# plinkykeeb2_21Jan2022.net
KiCad netlist of a schematic drawn in EAGLE
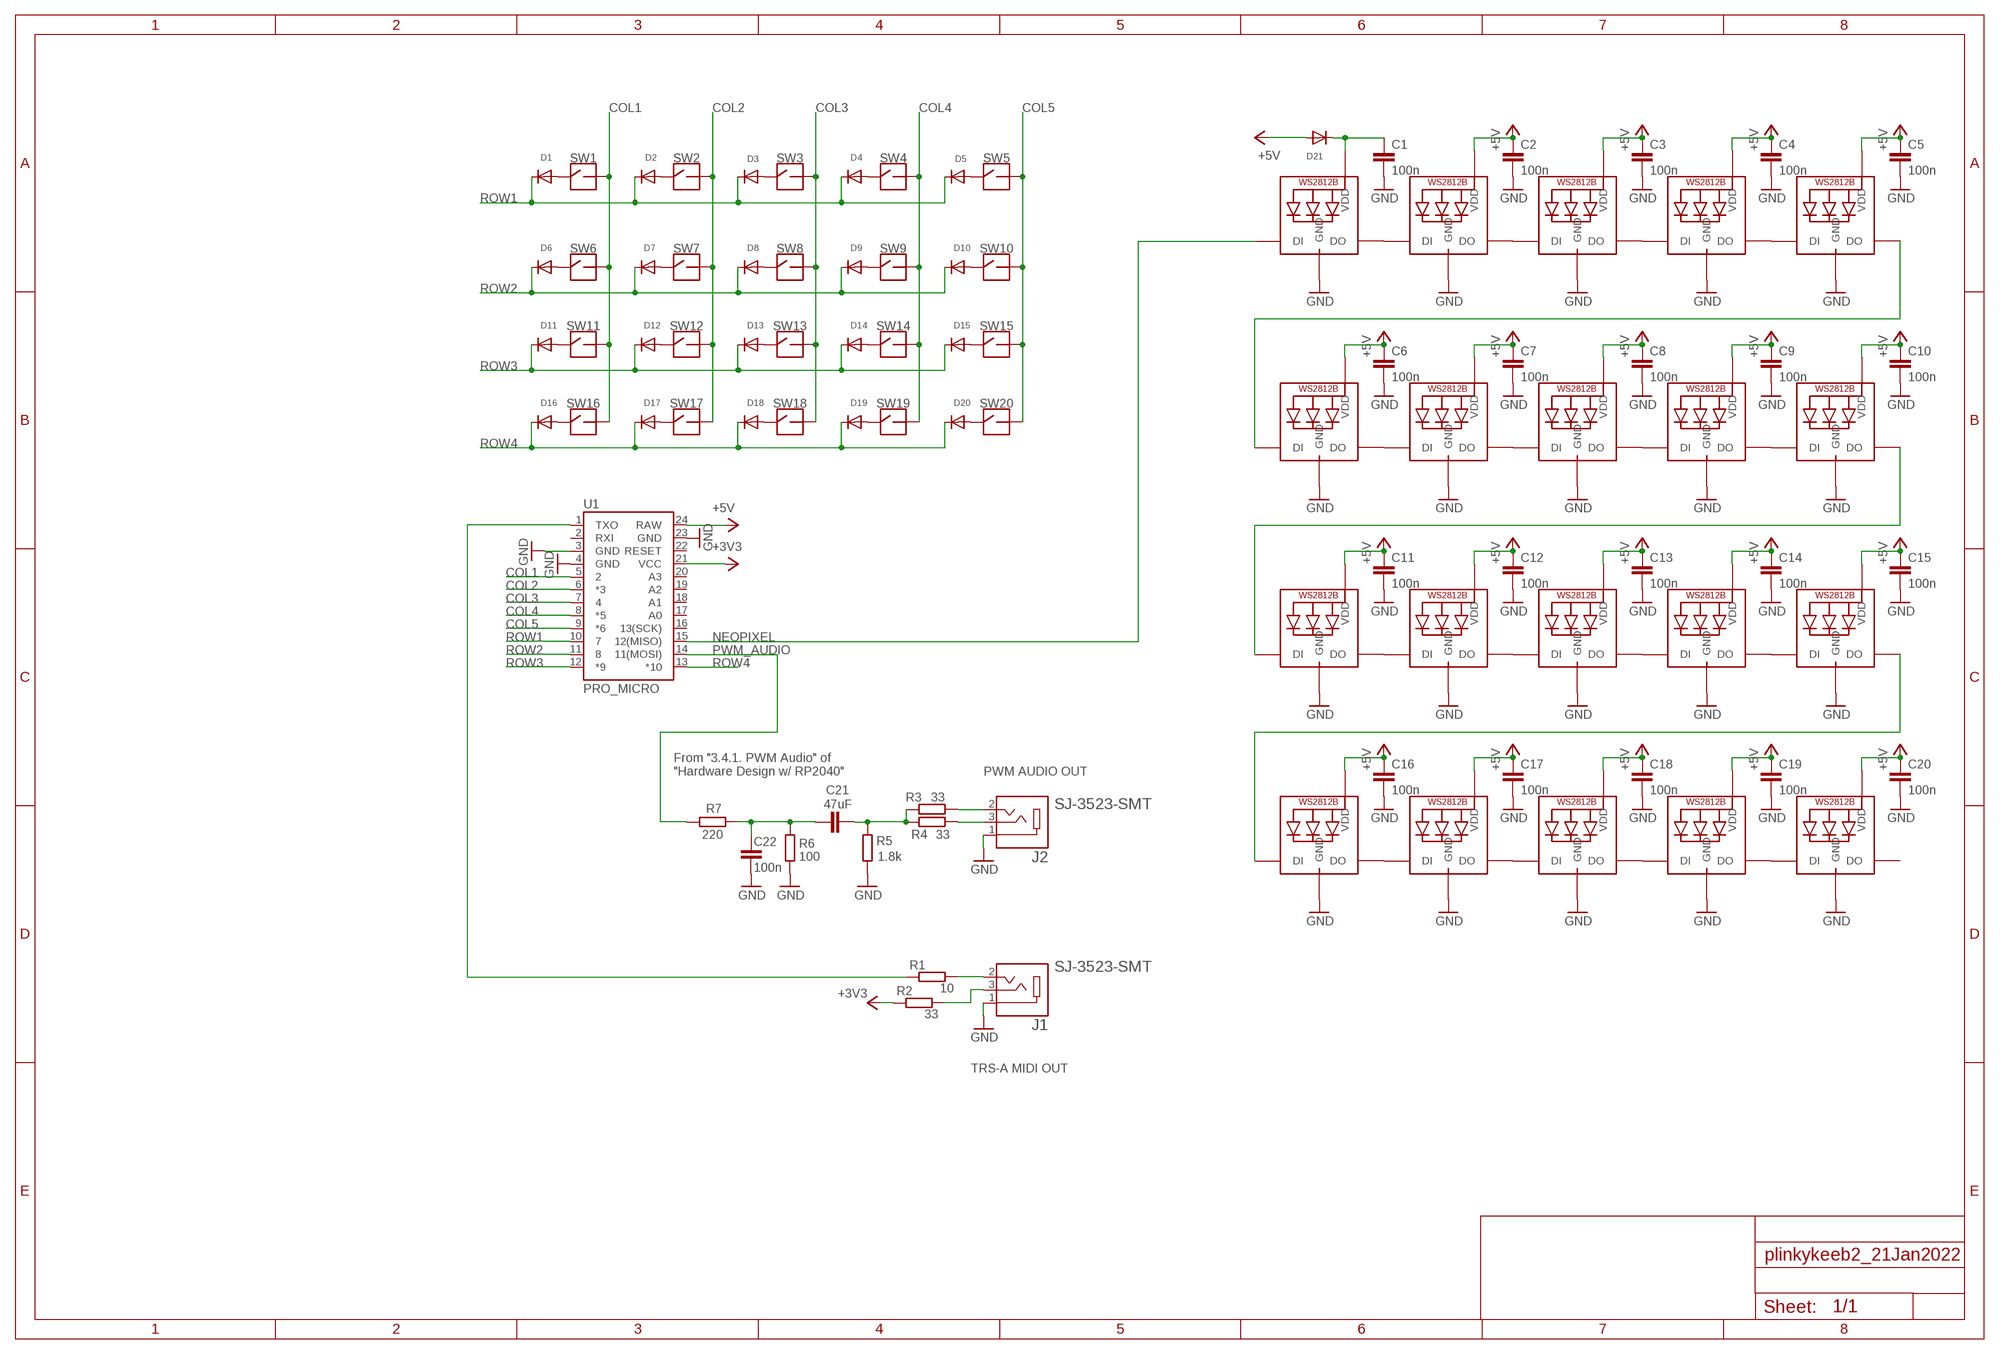
[diagram p0: schematic, sheet 1]

(export (version "E")
  (design (tool "Eeschema 10.0.6"))
  (components
    (comp (ref "C1")
      (value "100n")
      (footprint "eagle-import:C025-024X044")
      (libsource (lib "eagle-import") (part "C-EU025-024X044"))
    )
    (comp (ref "C2")
      (value "100n")
      (footprint "eagle-import:C025-024X044")
      (libsource (lib "eagle-import") (part "C-EU025-024X044"))
    )
    (comp (ref "C3")
      (value "100n")
      (footprint "eagle-import:C025-024X044")
      (libsource (lib "eagle-import") (part "C-EU025-024X044"))
    )
    (comp (ref "C4")
      (value "100n")
      (footprint "eagle-import:C025-024X044")
      (libsource (lib "eagle-import") (part "C-EU025-024X044"))
    )
    (comp (ref "C5")
      (value "100n")
      (footprint "eagle-import:C025-024X044")
      (libsource (lib "eagle-import") (part "C-EU025-024X044"))
    )
    (comp (ref "C6")
      (value "100n")
      (footprint "eagle-import:C025-024X044")
      (libsource (lib "eagle-import") (part "C-EU025-024X044"))
    )
    (comp (ref "C7")
      (value "100n")
      (footprint "eagle-import:C025-024X044")
      (libsource (lib "eagle-import") (part "C-EU025-024X044"))
    )
    (comp (ref "C8")
      (value "100n")
      (footprint "eagle-import:C025-024X044")
      (libsource (lib "eagle-import") (part "C-EU025-024X044"))
    )
    (comp (ref "C9")
      (value "100n")
      (footprint "eagle-import:C025-024X044")
      (libsource (lib "eagle-import") (part "C-EU025-024X044"))
    )
    (comp (ref "C10")
      (value "100n")
      (footprint "eagle-import:C025-024X044")
      (libsource (lib "eagle-import") (part "C-EU025-024X044"))
    )
    (comp (ref "C11")
      (value "100n")
      (footprint "eagle-import:C025-024X044")
      (libsource (lib "eagle-import") (part "C-EU025-024X044"))
    )
    (comp (ref "C12")
      (value "100n")
      (footprint "eagle-import:C025-024X044")
      (libsource (lib "eagle-import") (part "C-EU025-024X044"))
    )
    (comp (ref "C13")
      (value "100n")
      (footprint "eagle-import:C025-024X044")
      (libsource (lib "eagle-import") (part "C-EU025-024X044"))
    )
    (comp (ref "C14")
      (value "100n")
      (footprint "eagle-import:C025-024X044")
      (libsource (lib "eagle-import") (part "C-EU025-024X044"))
    )
    (comp (ref "C15")
      (value "100n")
      (footprint "eagle-import:C025-024X044")
      (libsource (lib "eagle-import") (part "C-EU025-024X044"))
    )
    (comp (ref "C16")
      (value "100n")
      (footprint "eagle-import:C025-024X044")
      (libsource (lib "eagle-import") (part "C-EU025-024X044"))
    )
    (comp (ref "C17")
      (value "100n")
      (footprint "eagle-import:C025-024X044")
      (libsource (lib "eagle-import") (part "C-EU025-024X044"))
    )
    (comp (ref "C18")
      (value "100n")
      (footprint "eagle-import:C025-024X044")
      (libsource (lib "eagle-import") (part "C-EU025-024X044"))
    )
    (comp (ref "C19")
      (value "100n")
      (footprint "eagle-import:C025-024X044")
      (libsource (lib "eagle-import") (part "C-EU025-024X044"))
    )
    (comp (ref "C20")
      (value "100n")
      (footprint "eagle-import:C025-024X044")
      (libsource (lib "eagle-import") (part "C-EU025-024X044"))
    )
    (comp (ref "C21")
      (value "47uF")
      (footprint "eagle-import:C0805")
      (libsource (lib "eagle-import") (part "C-EUC0805"))
    )
    (comp (ref "C22")
      (value "100n")
      (footprint "eagle-import:C0805")
      (libsource (lib "eagle-import") (part "C-EUC0805"))
    )
    (comp (ref "D1")
      (value "DIODEDO-1N4148")
      (footprint "eagle-import:DO-1N4148")
      (libsource (lib "eagle-import") (part "DIODEDO-1N4148"))
    )
    (comp (ref "D2")
      (value "DIODEDO-1N4148")
      (footprint "eagle-import:DO-1N4148")
      (libsource (lib "eagle-import") (part "DIODEDO-1N4148"))
    )
    (comp (ref "D3")
      (value "DIODEDO-1N4148")
      (footprint "eagle-import:DO-1N4148")
      (libsource (lib "eagle-import") (part "DIODEDO-1N4148"))
    )
    (comp (ref "D4")
      (value "DIODEDO-1N4148")
      (footprint "eagle-import:DO-1N4148")
      (libsource (lib "eagle-import") (part "DIODEDO-1N4148"))
    )
    (comp (ref "D5")
      (value "DIODEDO-1N4148")
      (footprint "eagle-import:DO-1N4148")
      (libsource (lib "eagle-import") (part "DIODEDO-1N4148"))
    )
    (comp (ref "D6")
      (value "DIODEDO-1N4148")
      (footprint "eagle-import:DO-1N4148")
      (libsource (lib "eagle-import") (part "DIODEDO-1N4148"))
    )
    (comp (ref "D7")
      (value "DIODEDO-1N4148")
      (footprint "eagle-import:DO-1N4148")
      (libsource (lib "eagle-import") (part "DIODEDO-1N4148"))
    )
    (comp (ref "D8")
      (value "DIODEDO-1N4148")
      (footprint "eagle-import:DO-1N4148")
      (libsource (lib "eagle-import") (part "DIODEDO-1N4148"))
    )
    (comp (ref "D9")
      (value "DIODEDO-1N4148")
      (footprint "eagle-import:DO-1N4148")
      (libsource (lib "eagle-import") (part "DIODEDO-1N4148"))
    )
    (comp (ref "D10")
      (value "DIODEDO-1N4148")
      (footprint "eagle-import:DO-1N4148")
      (libsource (lib "eagle-import") (part "DIODEDO-1N4148"))
    )
    (comp (ref "D11")
      (value "DIODEDO-1N4148")
      (footprint "eagle-import:DO-1N4148")
      (libsource (lib "eagle-import") (part "DIODEDO-1N4148"))
    )
    (comp (ref "D12")
      (value "DIODEDO-1N4148")
      (footprint "eagle-import:DO-1N4148")
      (libsource (lib "eagle-import") (part "DIODEDO-1N4148"))
    )
    (comp (ref "D13")
      (value "DIODEDO-1N4148")
      (footprint "eagle-import:DO-1N4148")
      (libsource (lib "eagle-import") (part "DIODEDO-1N4148"))
    )
    (comp (ref "D14")
      (value "DIODEDO-1N4148")
      (footprint "eagle-import:DO-1N4148")
      (libsource (lib "eagle-import") (part "DIODEDO-1N4148"))
    )
    (comp (ref "D15")
      (value "DIODEDO-1N4148")
      (footprint "eagle-import:DO-1N4148")
      (libsource (lib "eagle-import") (part "DIODEDO-1N4148"))
    )
    (comp (ref "D16")
      (value "DIODEDO-1N4148")
      (footprint "eagle-import:DO-1N4148")
      (libsource (lib "eagle-import") (part "DIODEDO-1N4148"))
    )
    (comp (ref "D17")
      (value "DIODEDO-1N4148")
      (footprint "eagle-import:DO-1N4148")
      (libsource (lib "eagle-import") (part "DIODEDO-1N4148"))
    )
    (comp (ref "D18")
      (value "DIODEDO-1N4148")
      (footprint "eagle-import:DO-1N4148")
      (libsource (lib "eagle-import") (part "DIODEDO-1N4148"))
    )
    (comp (ref "D19")
      (value "DIODEDO-1N4148")
      (footprint "eagle-import:DO-1N4148")
      (libsource (lib "eagle-import") (part "DIODEDO-1N4148"))
    )
    (comp (ref "D20")
      (value "DIODEDO-1N4148")
      (footprint "eagle-import:DO-1N4148")
      (libsource (lib "eagle-import") (part "DIODEDO-1N4148"))
    )
    (comp (ref "D21")
      (value "DIODEDO-1N4148")
      (footprint "eagle-import:DO-1N4148")
      (libsource (lib "eagle-import") (part "DIODEDO-1N4148"))
    )
    (comp (ref "J1")
      (value "SJ-3523-SMT")
      (footprint "eagle-import:CUI_SJ-3523-SMT")
      (fields
        (field (name "DIGI-KEY_PART_NUMBER") "CP-3523SJCT-ND")
        (field (name "MF") "CUI Devices")
        (field (name "MP") "SJ-3523-SMT-TR")
      )
      (libsource (lib "eagle-import") (part "SJ-3523-SMT"))
    )
    (comp (ref "J2")
      (value "SJ-3523-SMT")
      (footprint "eagle-import:CUI_SJ-3523-SMT")
      (fields
        (field (name "DIGI-KEY_PART_NUMBER") "CP-3523SJCT-ND")
        (field (name "MF") "CUI Devices")
        (field (name "MP") "SJ-3523-SMT-TR")
      )
      (libsource (lib "eagle-import") (part "SJ-3523-SMT"))
    )
    (comp (ref "LED1")
      (value "MICROBUILDER_WS2812B_SK6812E")
      (footprint "eagle-import:MICROBUILDER_NEO3535_REVERSE")
      (libsource (lib "eagle-import") (part "MICROBUILDER_WS2812B_SK6812E"))
    )
    (comp (ref "LED2")
      (value "MICROBUILDER_WS2812B_SK6812E")
      (footprint "eagle-import:MICROBUILDER_NEO3535_REVERSE")
      (libsource (lib "eagle-import") (part "MICROBUILDER_WS2812B_SK6812E"))
    )
    (comp (ref "LED3")
      (value "MICROBUILDER_WS2812B_SK6812E")
      (footprint "eagle-import:MICROBUILDER_NEO3535_REVERSE")
      (libsource (lib "eagle-import") (part "MICROBUILDER_WS2812B_SK6812E"))
    )
    (comp (ref "LED4")
      (value "MICROBUILDER_WS2812B_SK6812E")
      (footprint "eagle-import:MICROBUILDER_NEO3535_REVERSE")
      (libsource (lib "eagle-import") (part "MICROBUILDER_WS2812B_SK6812E"))
    )
    (comp (ref "LED5")
      (value "MICROBUILDER_WS2812B_SK6812E")
      (footprint "eagle-import:MICROBUILDER_NEO3535_REVERSE")
      (libsource (lib "eagle-import") (part "MICROBUILDER_WS2812B_SK6812E"))
    )
    (comp (ref "LED6")
      (value "MICROBUILDER_WS2812B_SK6812E")
      (footprint "eagle-import:MICROBUILDER_NEO3535_REVERSE")
      (libsource (lib "eagle-import") (part "MICROBUILDER_WS2812B_SK6812E"))
    )
    (comp (ref "LED7")
      (value "MICROBUILDER_WS2812B_SK6812E")
      (footprint "eagle-import:MICROBUILDER_NEO3535_REVERSE")
      (libsource (lib "eagle-import") (part "MICROBUILDER_WS2812B_SK6812E"))
    )
    (comp (ref "LED8")
      (value "MICROBUILDER_WS2812B_SK6812E")
      (footprint "eagle-import:MICROBUILDER_NEO3535_REVERSE")
      (libsource (lib "eagle-import") (part "MICROBUILDER_WS2812B_SK6812E"))
    )
    (comp (ref "LED9")
      (value "MICROBUILDER_WS2812B_SK6812E")
      (footprint "eagle-import:MICROBUILDER_NEO3535_REVERSE")
      (libsource (lib "eagle-import") (part "MICROBUILDER_WS2812B_SK6812E"))
    )
    (comp (ref "LED10")
      (value "MICROBUILDER_WS2812B_SK6812E")
      (footprint "eagle-import:MICROBUILDER_NEO3535_REVERSE")
      (libsource (lib "eagle-import") (part "MICROBUILDER_WS2812B_SK6812E"))
    )
    (comp (ref "LED11")
      (value "MICROBUILDER_WS2812B_SK6812E")
      (footprint "eagle-import:MICROBUILDER_NEO3535_REVERSE")
      (libsource (lib "eagle-import") (part "MICROBUILDER_WS2812B_SK6812E"))
    )
    (comp (ref "LED12")
      (value "MICROBUILDER_WS2812B_SK6812E")
      (footprint "eagle-import:MICROBUILDER_NEO3535_REVERSE")
      (libsource (lib "eagle-import") (part "MICROBUILDER_WS2812B_SK6812E"))
    )
    (comp (ref "LED13")
      (value "MICROBUILDER_WS2812B_SK6812E")
      (footprint "eagle-import:MICROBUILDER_NEO3535_REVERSE")
      (libsource (lib "eagle-import") (part "MICROBUILDER_WS2812B_SK6812E"))
    )
    (comp (ref "LED14")
      (value "MICROBUILDER_WS2812B_SK6812E")
      (footprint "eagle-import:MICROBUILDER_NEO3535_REVERSE")
      (libsource (lib "eagle-import") (part "MICROBUILDER_WS2812B_SK6812E"))
    )
    (comp (ref "LED15")
      (value "MICROBUILDER_WS2812B_SK6812E")
      (footprint "eagle-import:MICROBUILDER_NEO3535_REVERSE")
      (libsource (lib "eagle-import") (part "MICROBUILDER_WS2812B_SK6812E"))
    )
    (comp (ref "LED16")
      (value "MICROBUILDER_WS2812B_SK6812E")
      (footprint "eagle-import:MICROBUILDER_NEO3535_REVERSE")
      (libsource (lib "eagle-import") (part "MICROBUILDER_WS2812B_SK6812E"))
    )
    (comp (ref "LED17")
      (value "MICROBUILDER_WS2812B_SK6812E")
      (footprint "eagle-import:MICROBUILDER_NEO3535_REVERSE")
      (libsource (lib "eagle-import") (part "MICROBUILDER_WS2812B_SK6812E"))
    )
    (comp (ref "LED18")
      (value "MICROBUILDER_WS2812B_SK6812E")
      (footprint "eagle-import:MICROBUILDER_NEO3535_REVERSE")
      (libsource (lib "eagle-import") (part "MICROBUILDER_WS2812B_SK6812E"))
    )
    (comp (ref "LED19")
      (value "MICROBUILDER_WS2812B_SK6812E")
      (footprint "eagle-import:MICROBUILDER_NEO3535_REVERSE")
      (libsource (lib "eagle-import") (part "MICROBUILDER_WS2812B_SK6812E"))
    )
    (comp (ref "LED20")
      (value "MICROBUILDER_WS2812B_SK6812E")
      (footprint "eagle-import:MICROBUILDER_NEO3535_REVERSE")
      (libsource (lib "eagle-import") (part "MICROBUILDER_WS2812B_SK6812E"))
    )
    (comp (ref "R1")
      (value "10")
      (footprint "eagle-import:R0805")
      (libsource (lib "eagle-import") (part "R-EU_R0805"))
    )
    (comp (ref "R2")
      (value "33")
      (footprint "eagle-import:R0805")
      (libsource (lib "eagle-import") (part "R-EU_R0805"))
    )
    (comp (ref "R3")
      (value "33")
      (footprint "eagle-import:R0805")
      (libsource (lib "eagle-import") (part "R-EU_R0805"))
    )
    (comp (ref "R4")
      (value "33")
      (footprint "eagle-import:R0805")
      (libsource (lib "eagle-import") (part "R-EU_R0805"))
    )
    (comp (ref "R5")
      (value "1.8k")
      (footprint "eagle-import:R0805")
      (libsource (lib "eagle-import") (part "R-EU_R0805"))
    )
    (comp (ref "R6")
      (value "100")
      (footprint "eagle-import:R0805")
      (libsource (lib "eagle-import") (part "R-EU_R0805"))
    )
    (comp (ref "R7")
      (value "220")
      (footprint "eagle-import:R0805")
      (libsource (lib "eagle-import") (part "R-EU_R0805"))
    )
    (comp (ref "SW1")
      (value "KAILH_SOCKETBOX_JADE")
      (footprint "eagle-import:ADAFRUIT_ELECTROMECH_KAILH_SOCKET")
      (libsource (lib "eagle-import") (part "ADAFRUIT_ELECTROMECH_KBD_SWITCH_KAILH_SOCKETBOX_JADE_KAILH_SOCKET"))
    )
    (comp (ref "SW2")
      (value "KAILH_SOCKETBOX_JADE")
      (footprint "eagle-import:ADAFRUIT_ELECTROMECH_KAILH_SOCKET")
      (libsource (lib "eagle-import") (part "ADAFRUIT_ELECTROMECH_KBD_SWITCH_KAILH_SOCKETBOX_JADE_KAILH_SOCKET"))
    )
    (comp (ref "SW3")
      (value "KAILH_SOCKETBOX_JADE")
      (footprint "eagle-import:ADAFRUIT_ELECTROMECH_KAILH_SOCKET")
      (libsource (lib "eagle-import") (part "ADAFRUIT_ELECTROMECH_KBD_SWITCH_KAILH_SOCKETBOX_JADE_KAILH_SOCKET"))
    )
    (comp (ref "SW4")
      (value "KAILH_SOCKETBOX_JADE")
      (footprint "eagle-import:ADAFRUIT_ELECTROMECH_KAILH_SOCKET")
      (libsource (lib "eagle-import") (part "ADAFRUIT_ELECTROMECH_KBD_SWITCH_KAILH_SOCKETBOX_JADE_KAILH_SOCKET"))
    )
    (comp (ref "SW5")
      (value "KAILH_SOCKETBOX_JADE")
      (footprint "eagle-import:ADAFRUIT_ELECTROMECH_KAILH_SOCKET")
      (libsource (lib "eagle-import") (part "ADAFRUIT_ELECTROMECH_KBD_SWITCH_KAILH_SOCKETBOX_JADE_KAILH_SOCKET"))
    )
    (comp (ref "SW6")
      (value "KAILH_SOCKETBOX_JADE")
      (footprint "eagle-import:ADAFRUIT_ELECTROMECH_KAILH_SOCKET")
      (libsource (lib "eagle-import") (part "ADAFRUIT_ELECTROMECH_KBD_SWITCH_KAILH_SOCKETBOX_JADE_KAILH_SOCKET"))
    )
    (comp (ref "SW7")
      (value "KAILH_SOCKETBOX_JADE")
      (footprint "eagle-import:ADAFRUIT_ELECTROMECH_KAILH_SOCKET")
      (libsource (lib "eagle-import") (part "ADAFRUIT_ELECTROMECH_KBD_SWITCH_KAILH_SOCKETBOX_JADE_KAILH_SOCKET"))
    )
    (comp (ref "SW8")
      (value "KAILH_SOCKETBOX_JADE")
      (footprint "eagle-import:ADAFRUIT_ELECTROMECH_KAILH_SOCKET")
      (libsource (lib "eagle-import") (part "ADAFRUIT_ELECTROMECH_KBD_SWITCH_KAILH_SOCKETBOX_JADE_KAILH_SOCKET"))
    )
    (comp (ref "SW9")
      (value "KAILH_SOCKETBOX_JADE")
      (footprint "eagle-import:ADAFRUIT_ELECTROMECH_KAILH_SOCKET")
      (libsource (lib "eagle-import") (part "ADAFRUIT_ELECTROMECH_KBD_SWITCH_KAILH_SOCKETBOX_JADE_KAILH_SOCKET"))
    )
    (comp (ref "SW10")
      (value "KAILH_SOCKETBOX_JADE")
      (footprint "eagle-import:ADAFRUIT_ELECTROMECH_KAILH_SOCKET")
      (libsource (lib "eagle-import") (part "ADAFRUIT_ELECTROMECH_KBD_SWITCH_KAILH_SOCKETBOX_JADE_KAILH_SOCKET"))
    )
    (comp (ref "SW11")
      (value "KAILH_SOCKETBOX_JADE")
      (footprint "eagle-import:ADAFRUIT_ELECTROMECH_KAILH_SOCKET")
      (libsource (lib "eagle-import") (part "ADAFRUIT_ELECTROMECH_KBD_SWITCH_KAILH_SOCKETBOX_JADE_KAILH_SOCKET"))
    )
    (comp (ref "SW12")
      (value "KAILH_SOCKETBOX_JADE")
      (footprint "eagle-import:ADAFRUIT_ELECTROMECH_KAILH_SOCKET")
      (libsource (lib "eagle-import") (part "ADAFRUIT_ELECTROMECH_KBD_SWITCH_KAILH_SOCKETBOX_JADE_KAILH_SOCKET"))
    )
    (comp (ref "SW13")
      (value "KAILH_SOCKETBOX_JADE")
      (footprint "eagle-import:ADAFRUIT_ELECTROMECH_KAILH_SOCKET")
      (libsource (lib "eagle-import") (part "ADAFRUIT_ELECTROMECH_KBD_SWITCH_KAILH_SOCKETBOX_JADE_KAILH_SOCKET"))
    )
    (comp (ref "SW14")
      (value "KAILH_SOCKETBOX_JADE")
      (footprint "eagle-import:ADAFRUIT_ELECTROMECH_KAILH_SOCKET")
      (libsource (lib "eagle-import") (part "ADAFRUIT_ELECTROMECH_KBD_SWITCH_KAILH_SOCKETBOX_JADE_KAILH_SOCKET"))
    )
    (comp (ref "SW15")
      (value "KAILH_SOCKETBOX_JADE")
      (footprint "eagle-import:ADAFRUIT_ELECTROMECH_KAILH_SOCKET")
      (libsource (lib "eagle-import") (part "ADAFRUIT_ELECTROMECH_KBD_SWITCH_KAILH_SOCKETBOX_JADE_KAILH_SOCKET"))
    )
    (comp (ref "SW16")
      (value "KAILH_SOCKETBOX_JADE")
      (footprint "eagle-import:ADAFRUIT_ELECTROMECH_KAILH_SOCKET")
      (libsource (lib "eagle-import") (part "ADAFRUIT_ELECTROMECH_KBD_SWITCH_KAILH_SOCKETBOX_JADE_KAILH_SOCKET"))
    )
    (comp (ref "SW17")
      (value "KAILH_SOCKETBOX_JADE")
      (footprint "eagle-import:ADAFRUIT_ELECTROMECH_KAILH_SOCKET")
      (libsource (lib "eagle-import") (part "ADAFRUIT_ELECTROMECH_KBD_SWITCH_KAILH_SOCKETBOX_JADE_KAILH_SOCKET"))
    )
    (comp (ref "SW18")
      (value "KAILH_SOCKETBOX_JADE")
      (footprint "eagle-import:ADAFRUIT_ELECTROMECH_KAILH_SOCKET")
      (libsource (lib "eagle-import") (part "ADAFRUIT_ELECTROMECH_KBD_SWITCH_KAILH_SOCKETBOX_JADE_KAILH_SOCKET"))
    )
    (comp (ref "SW19")
      (value "KAILH_SOCKETBOX_JADE")
      (footprint "eagle-import:ADAFRUIT_ELECTROMECH_KAILH_SOCKET")
      (libsource (lib "eagle-import") (part "ADAFRUIT_ELECTROMECH_KBD_SWITCH_KAILH_SOCKETBOX_JADE_KAILH_SOCKET"))
    )
    (comp (ref "SW20")
      (value "KAILH_SOCKETBOX_JADE")
      (footprint "eagle-import:ADAFRUIT_ELECTROMECH_KAILH_SOCKET")
      (libsource (lib "eagle-import") (part "ADAFRUIT_ELECTROMECH_KBD_SWITCH_KAILH_SOCKETBOX_JADE_KAILH_SOCKET"))
    )
    (comp (ref "U1")
      (value "PRO_MICRO")
      (footprint "eagle-import:SPARKFUN_PRO_MICRO")
      (libsource (lib "eagle-import") (part "SPARKFUN_PRO_MICRO"))
    )
  )
  (nets
    (net (code "1") (name "+3V3") (class "Default")
      (node (ref "R2") (pin "2") (pinfunction "2_2") (pintype "passive"))
      (node (ref "U1") (pin "21") (pinfunction "VCC_21") (pintype "power_in"))
    )
    (net (code "2") (name "+5V") (class "Default")
      (node (ref "C10") (pin "1") (pinfunction "1_1") (pintype "passive"))
      (node (ref "C11") (pin "1") (pinfunction "1_1") (pintype "passive"))
      (node (ref "C12") (pin "1") (pinfunction "1_1") (pintype "passive"))
      (node (ref "C13") (pin "1") (pinfunction "1_1") (pintype "passive"))
      (node (ref "C14") (pin "1") (pinfunction "1_1") (pintype "passive"))
      (node (ref "C15") (pin "1") (pinfunction "1_1") (pintype "passive"))
      (node (ref "C16") (pin "1") (pinfunction "1_1") (pintype "passive"))
      (node (ref "C17") (pin "1") (pinfunction "1_1") (pintype "passive"))
      (node (ref "C18") (pin "1") (pinfunction "1_1") (pintype "passive"))
      (node (ref "C19") (pin "1") (pinfunction "1_1") (pintype "passive"))
      (node (ref "C2") (pin "1") (pinfunction "1_1") (pintype "passive"))
      (node (ref "C20") (pin "1") (pinfunction "1_1") (pintype "passive"))
      (node (ref "C3") (pin "1") (pinfunction "1_1") (pintype "passive"))
      (node (ref "C4") (pin "1") (pinfunction "1_1") (pintype "passive"))
      (node (ref "C5") (pin "1") (pinfunction "1_1") (pintype "passive"))
      (node (ref "C6") (pin "1") (pinfunction "1_1") (pintype "passive"))
      (node (ref "C7") (pin "1") (pinfunction "1_1") (pintype "passive"))
      (node (ref "C8") (pin "1") (pinfunction "1_1") (pintype "passive"))
      (node (ref "C9") (pin "1") (pinfunction "1_1") (pintype "passive"))
      (node (ref "D21") (pin "A") (pinfunction "A_A") (pintype "passive"))
      (node (ref "LED10") (pin "1-VDD") (pinfunction "VDD_1-VDD") (pintype "power_in"))
      (node (ref "LED11") (pin "1-VDD") (pinfunction "VDD_1-VDD") (pintype "power_in"))
      (node (ref "LED12") (pin "1-VDD") (pinfunction "VDD_1-VDD") (pintype "power_in"))
      (node (ref "LED13") (pin "1-VDD") (pinfunction "VDD_1-VDD") (pintype "power_in"))
      (node (ref "LED14") (pin "1-VDD") (pinfunction "VDD_1-VDD") (pintype "power_in"))
      (node (ref "LED15") (pin "1-VDD") (pinfunction "VDD_1-VDD") (pintype "power_in"))
      (node (ref "LED16") (pin "1-VDD") (pinfunction "VDD_1-VDD") (pintype "power_in"))
      (node (ref "LED17") (pin "1-VDD") (pinfunction "VDD_1-VDD") (pintype "power_in"))
      (node (ref "LED18") (pin "1-VDD") (pinfunction "VDD_1-VDD") (pintype "power_in"))
      (node (ref "LED19") (pin "1-VDD") (pinfunction "VDD_1-VDD") (pintype "power_in"))
      (node (ref "LED2") (pin "1-VDD") (pinfunction "VDD_1-VDD") (pintype "power_in"))
      (node (ref "LED20") (pin "1-VDD") (pinfunction "VDD_1-VDD") (pintype "power_in"))
      (node (ref "LED3") (pin "1-VDD") (pinfunction "VDD_1-VDD") (pintype "power_in"))
      (node (ref "LED4") (pin "1-VDD") (pinfunction "VDD_1-VDD") (pintype "power_in"))
      (node (ref "LED5") (pin "1-VDD") (pinfunction "VDD_1-VDD") (pintype "power_in"))
      (node (ref "LED6") (pin "1-VDD") (pinfunction "VDD_1-VDD") (pintype "power_in"))
      (node (ref "LED7") (pin "1-VDD") (pinfunction "VDD_1-VDD") (pintype "power_in"))
      (node (ref "LED8") (pin "1-VDD") (pinfunction "VDD_1-VDD") (pintype "power_in"))
      (node (ref "LED9") (pin "1-VDD") (pinfunction "VDD_1-VDD") (pintype "power_in"))
      (node (ref "U1") (pin "24") (pinfunction "RAW_24") (pintype "power_in"))
    )
    (net (code "3") (name "/COL1") (class "Default")
      (node (ref "SW1") (pin "2") (pinfunction "2_2") (pintype "passive"))
      (node (ref "SW11") (pin "2") (pinfunction "2_2") (pintype "passive"))
      (node (ref "SW16") (pin "2") (pinfunction "2_2") (pintype "passive"))
      (node (ref "SW6") (pin "2") (pinfunction "2_2") (pintype "passive"))
      (node (ref "U1") (pin "5") (pinfunction "2_5") (pintype "bidirectional"))
    )
    (net (code "4") (name "/COL2") (class "Default")
      (node (ref "SW12") (pin "2") (pinfunction "2_2") (pintype "passive"))
      (node (ref "SW17") (pin "2") (pinfunction "2_2") (pintype "passive"))
      (node (ref "SW2") (pin "2") (pinfunction "2_2") (pintype "passive"))
      (node (ref "SW7") (pin "2") (pinfunction "2_2") (pintype "passive"))
      (node (ref "U1") (pin "6") (pinfunction "*3_6") (pintype "bidirectional"))
    )
    (net (code "5") (name "/COL3") (class "Default")
      (node (ref "SW13") (pin "2") (pinfunction "2_2") (pintype "passive"))
      (node (ref "SW18") (pin "2") (pinfunction "2_2") (pintype "passive"))
      (node (ref "SW3") (pin "2") (pinfunction "2_2") (pintype "passive"))
      (node (ref "SW8") (pin "2") (pinfunction "2_2") (pintype "passive"))
      (node (ref "U1") (pin "7") (pinfunction "4_7") (pintype "bidirectional"))
    )
    (net (code "6") (name "/COL4") (class "Default")
      (node (ref "SW14") (pin "2") (pinfunction "2_2") (pintype "passive"))
      (node (ref "SW19") (pin "2") (pinfunction "2_2") (pintype "passive"))
      (node (ref "SW4") (pin "2") (pinfunction "2_2") (pintype "passive"))
      (node (ref "SW9") (pin "2") (pinfunction "2_2") (pintype "passive"))
      (node (ref "U1") (pin "8") (pinfunction "*5_8") (pintype "bidirectional"))
    )
    (net (code "7") (name "/COL5") (class "Default")
      (node (ref "SW10") (pin "2") (pinfunction "2_2") (pintype "passive"))
      (node (ref "SW15") (pin "2") (pinfunction "2_2") (pintype "passive"))
      (node (ref "SW20") (pin "2") (pinfunction "2_2") (pintype "passive"))
      (node (ref "SW5") (pin "2") (pinfunction "2_2") (pintype "passive"))
      (node (ref "U1") (pin "9") (pinfunction "*6_9") (pintype "bidirectional"))
    )
    (net (code "8") (name "/NEOPIXEL") (class "Default")
      (node (ref "LED1") (pin "4-DIN") (pinfunction "DI_4-DIN") (pintype "input"))
      (node (ref "U1") (pin "15") (pinfunction "12(MISO)_15") (pintype "bidirectional"))
    )
    (net (code "9") (name "/PWM_AUDIO") (class "Default")
      (node (ref "R7") (pin "2") (pinfunction "2_2") (pintype "passive"))
      (node (ref "U1") (pin "14") (pinfunction "11(MOSI)_14") (pintype "bidirectional"))
    )
    (net (code "10") (name "/ROW1") (class "Default")
      (node (ref "D1") (pin "C") (pinfunction "C_C") (pintype "passive"))
      (node (ref "D2") (pin "C") (pinfunction "C_C") (pintype "passive"))
      (node (ref "D3") (pin "C") (pinfunction "C_C") (pintype "passive"))
      (node (ref "D4") (pin "C") (pinfunction "C_C") (pintype "passive"))
      (node (ref "D5") (pin "C") (pinfunction "C_C") (pintype "passive"))
      (node (ref "U1") (pin "10") (pinfunction "7_10") (pintype "bidirectional"))
    )
    (net (code "11") (name "/ROW2") (class "Default")
      (node (ref "D10") (pin "C") (pinfunction "C_C") (pintype "passive"))
      (node (ref "D6") (pin "C") (pinfunction "C_C") (pintype "passive"))
      (node (ref "D7") (pin "C") (pinfunction "C_C") (pintype "passive"))
      (node (ref "D8") (pin "C") (pinfunction "C_C") (pintype "passive"))
      (node (ref "D9") (pin "C") (pinfunction "C_C") (pintype "passive"))
      (node (ref "U1") (pin "11") (pinfunction "8_11") (pintype "bidirectional"))
    )
    (net (code "12") (name "/ROW3") (class "Default")
      (node (ref "D11") (pin "C") (pinfunction "C_C") (pintype "passive"))
      (node (ref "D12") (pin "C") (pinfunction "C_C") (pintype "passive"))
      (node (ref "D13") (pin "C") (pinfunction "C_C") (pintype "passive"))
      (node (ref "D14") (pin "C") (pinfunction "C_C") (pintype "passive"))
      (node (ref "D15") (pin "C") (pinfunction "C_C") (pintype "passive"))
      (node (ref "U1") (pin "12") (pinfunction "*9_12") (pintype "bidirectional"))
    )
    (net (code "13") (name "/ROW4") (class "Default")
      (node (ref "D16") (pin "C") (pinfunction "C_C") (pintype "passive"))
      (node (ref "D17") (pin "C") (pinfunction "C_C") (pintype "passive"))
      (node (ref "D18") (pin "C") (pinfunction "C_C") (pintype "passive"))
      (node (ref "D19") (pin "C") (pinfunction "C_C") (pintype "passive"))
      (node (ref "D20") (pin "C") (pinfunction "C_C") (pintype "passive"))
      (node (ref "U1") (pin "13") (pinfunction "*10_13") (pintype "bidirectional"))
    )
    (net (code "14") (name "GND") (class "Default")
      (node (ref "C1") (pin "2") (pinfunction "2_2") (pintype "passive"))
      (node (ref "C10") (pin "2") (pinfunction "2_2") (pintype "passive"))
      (node (ref "C11") (pin "2") (pinfunction "2_2") (pintype "passive"))
      (node (ref "C12") (pin "2") (pinfunction "2_2") (pintype "passive"))
      (node (ref "C13") (pin "2") (pinfunction "2_2") (pintype "passive"))
      (node (ref "C14") (pin "2") (pinfunction "2_2") (pintype "passive"))
      (node (ref "C15") (pin "2") (pinfunction "2_2") (pintype "passive"))
      (node (ref "C16") (pin "2") (pinfunction "2_2") (pintype "passive"))
      (node (ref "C17") (pin "2") (pinfunction "2_2") (pintype "passive"))
      (node (ref "C18") (pin "2") (pinfunction "2_2") (pintype "passive"))
      (node (ref "C19") (pin "2") (pinfunction "2_2") (pintype "passive"))
      (node (ref "C2") (pin "2") (pinfunction "2_2") (pintype "passive"))
      (node (ref "C20") (pin "2") (pinfunction "2_2") (pintype "passive"))
      (node (ref "C22") (pin "2") (pinfunction "2_2") (pintype "passive"))
      (node (ref "C3") (pin "2") (pinfunction "2_2") (pintype "passive"))
      (node (ref "C4") (pin "2") (pinfunction "2_2") (pintype "passive"))
      (node (ref "C5") (pin "2") (pinfunction "2_2") (pintype "passive"))
      (node (ref "C6") (pin "2") (pinfunction "2_2") (pintype "passive"))
      (node (ref "C7") (pin "2") (pinfunction "2_2") (pintype "passive"))
      (node (ref "C8") (pin "2") (pinfunction "2_2") (pintype "passive"))
      (node (ref "C9") (pin "2") (pinfunction "2_2") (pintype "passive"))
      (node (ref "J1") (pin "1") (pinfunction "1_1") (pintype "passive"))
      (node (ref "J2") (pin "1") (pinfunction "1_1") (pintype "passive"))
      (node (ref "LED1") (pin "3-GND") (pinfunction "GND_3-GND") (pintype "power_in"))
      (node (ref "LED10") (pin "3-GND") (pinfunction "GND_3-GND") (pintype "power_in"))
      (node (ref "LED11") (pin "3-GND") (pinfunction "GND_3-GND") (pintype "power_in"))
      (node (ref "LED12") (pin "3-GND") (pinfunction "GND_3-GND") (pintype "power_in"))
      (node (ref "LED13") (pin "3-GND") (pinfunction "GND_3-GND") (pintype "power_in"))
      (node (ref "LED14") (pin "3-GND") (pinfunction "GND_3-GND") (pintype "power_in"))
      (node (ref "LED15") (pin "3-GND") (pinfunction "GND_3-GND") (pintype "power_in"))
      (node (ref "LED16") (pin "3-GND") (pinfunction "GND_3-GND") (pintype "power_in"))
      (node (ref "LED17") (pin "3-GND") (pinfunction "GND_3-GND") (pintype "power_in"))
      (node (ref "LED18") (pin "3-GND") (pinfunction "GND_3-GND") (pintype "power_in"))
      (node (ref "LED19") (pin "3-GND") (pinfunction "GND_3-GND") (pintype "power_in"))
      (node (ref "LED2") (pin "3-GND") (pinfunction "GND_3-GND") (pintype "power_in"))
      (node (ref "LED20") (pin "3-GND") (pinfunction "GND_3-GND") (pintype "power_in"))
      (node (ref "LED3") (pin "3-GND") (pinfunction "GND_3-GND") (pintype "power_in"))
      (node (ref "LED4") (pin "3-GND") (pinfunction "GND_3-GND") (pintype "power_in"))
      (node (ref "LED5") (pin "3-GND") (pinfunction "GND_3-GND") (pintype "power_in"))
      (node (ref "LED6") (pin "3-GND") (pinfunction "GND_3-GND") (pintype "power_in"))
      (node (ref "LED7") (pin "3-GND") (pinfunction "GND_3-GND") (pintype "power_in"))
      (node (ref "LED8") (pin "3-GND") (pinfunction "GND_3-GND") (pintype "power_in"))
      (node (ref "LED9") (pin "3-GND") (pinfunction "GND_3-GND") (pintype "power_in"))
      (node (ref "R5") (pin "2") (pinfunction "2_2") (pintype "passive"))
      (node (ref "R6") (pin "1") (pinfunction "1_1") (pintype "passive"))
      (node (ref "U1") (pin "23") (pinfunction "GND_23") (pintype "power_in"))
      (node (ref "U1") (pin "3") (pinfunction "GND_3") (pintype "power_in"))
      (node (ref "U1") (pin "4") (pinfunction "GND_4") (pintype "power_in"))
    )
    (net (code "15") (name "Net-(C21-Pad1)") (class "Default")
      (node (ref "C21") (pin "1") (pinfunction "1_1") (pintype "passive"))
      (node (ref "C22") (pin "1") (pinfunction "1_1") (pintype "passive"))
      (node (ref "R6") (pin "2") (pinfunction "2_2") (pintype "passive"))
      (node (ref "R7") (pin "1") (pinfunction "1_1") (pintype "passive"))
    )
    (net (code "16") (name "Net-(C21-Pad2)") (class "Default")
      (node (ref "C21") (pin "2") (pinfunction "2_2") (pintype "passive"))
      (node (ref "R3") (pin "2") (pinfunction "2_2") (pintype "passive"))
      (node (ref "R4") (pin "2") (pinfunction "2_2") (pintype "passive"))
      (node (ref "R5") (pin "1") (pinfunction "1_1") (pintype "passive"))
    )
    (net (code "17") (name "Net-(D1-PadA)") (class "Default")
      (node (ref "D1") (pin "A") (pinfunction "A_A") (pintype "passive"))
      (node (ref "SW1") (pin "1") (pinfunction "1_1") (pintype "passive"))
    )
    (net (code "18") (name "Net-(D2-PadA)") (class "Default")
      (node (ref "D2") (pin "A") (pinfunction "A_A") (pintype "passive"))
      (node (ref "SW2") (pin "1") (pinfunction "1_1") (pintype "passive"))
    )
    (net (code "19") (name "Net-(D3-PadA)") (class "Default")
      (node (ref "D3") (pin "A") (pinfunction "A_A") (pintype "passive"))
      (node (ref "SW3") (pin "1") (pinfunction "1_1") (pintype "passive"))
    )
    (net (code "20") (name "Net-(D4-PadA)") (class "Default")
      (node (ref "D4") (pin "A") (pinfunction "A_A") (pintype "passive"))
      (node (ref "SW4") (pin "1") (pinfunction "1_1") (pintype "passive"))
    )
    (net (code "21") (name "Net-(D5-PadA)") (class "Default")
      (node (ref "D5") (pin "A") (pinfunction "A_A") (pintype "passive"))
      (node (ref "SW5") (pin "1") (pinfunction "1_1") (pintype "passive"))
    )
    (net (code "22") (name "Net-(D6-PadA)") (class "Default")
      (node (ref "D6") (pin "A") (pinfunction "A_A") (pintype "passive"))
      (node (ref "SW6") (pin "1") (pinfunction "1_1") (pintype "passive"))
    )
    (net (code "23") (name "Net-(D7-PadA)") (class "Default")
      (node (ref "D7") (pin "A") (pinfunction "A_A") (pintype "passive"))
      (node (ref "SW7") (pin "1") (pinfunction "1_1") (pintype "passive"))
    )
    (net (code "24") (name "Net-(D8-PadA)") (class "Default")
      (node (ref "D8") (pin "A") (pinfunction "A_A") (pintype "passive"))
      (node (ref "SW8") (pin "1") (pinfunction "1_1") (pintype "passive"))
    )
    (net (code "25") (name "Net-(D9-PadA)") (class "Default")
      (node (ref "D9") (pin "A") (pinfunction "A_A") (pintype "passive"))
      (node (ref "SW9") (pin "1") (pinfunction "1_1") (pintype "passive"))
    )
    (net (code "26") (name "Net-(D10-PadA)") (class "Default")
      (node (ref "D10") (pin "A") (pinfunction "A_A") (pintype "passive"))
      (node (ref "SW10") (pin "1") (pinfunction "1_1") (pintype "passive"))
    )
    (net (code "27") (name "Net-(D11-PadA)") (class "Default")
      (node (ref "D11") (pin "A") (pinfunction "A_A") (pintype "passive"))
      (node (ref "SW11") (pin "1") (pinfunction "1_1") (pintype "passive"))
    )
    (net (code "28") (name "Net-(D12-PadA)") (class "Default")
      (node (ref "D12") (pin "A") (pinfunction "A_A") (pintype "passive"))
      (node (ref "SW12") (pin "1") (pinfunction "1_1") (pintype "passive"))
    )
    (net (code "29") (name "Net-(D13-PadA)") (class "Default")
      (node (ref "D13") (pin "A") (pinfunction "A_A") (pintype "passive"))
      (node (ref "SW13") (pin "1") (pinfunction "1_1") (pintype "passive"))
    )
    (net (code "30") (name "Net-(D14-PadA)") (class "Default")
      (node (ref "D14") (pin "A") (pinfunction "A_A") (pintype "passive"))
      (node (ref "SW14") (pin "1") (pinfunction "1_1") (pintype "passive"))
    )
    (net (code "31") (name "Net-(D15-PadA)") (class "Default")
      (node (ref "D15") (pin "A") (pinfunction "A_A") (pintype "passive"))
      (node (ref "SW15") (pin "1") (pinfunction "1_1") (pintype "passive"))
    )
    (net (code "32") (name "Net-(D16-PadA)") (class "Default")
      (node (ref "D16") (pin "A") (pinfunction "A_A") (pintype "passive"))
      (node (ref "SW16") (pin "1") (pinfunction "1_1") (pintype "passive"))
    )
    (net (code "33") (name "Net-(D17-PadA)") (class "Default")
      (node (ref "D17") (pin "A") (pinfunction "A_A") (pintype "passive"))
      (node (ref "SW17") (pin "1") (pinfunction "1_1") (pintype "passive"))
    )
    (net (code "34") (name "Net-(D18-PadA)") (class "Default")
      (node (ref "D18") (pin "A") (pinfunction "A_A") (pintype "passive"))
      (node (ref "SW18") (pin "1") (pinfunction "1_1") (pintype "passive"))
    )
    (net (code "35") (name "Net-(D19-PadA)") (class "Default")
      (node (ref "D19") (pin "A") (pinfunction "A_A") (pintype "passive"))
      (node (ref "SW19") (pin "1") (pinfunction "1_1") (pintype "passive"))
    )
    (net (code "36") (name "Net-(D20-PadA)") (class "Default")
      (node (ref "D20") (pin "A") (pinfunction "A_A") (pintype "passive"))
      (node (ref "SW20") (pin "1") (pinfunction "1_1") (pintype "passive"))
    )
    (net (code "37") (name "Net-(J1-Pad2)") (class "Default")
      (node (ref "J1") (pin "2") (pinfunction "2_2") (pintype "passive"))
      (node (ref "R1") (pin "1") (pinfunction "1_1") (pintype "passive"))
    )
    (net (code "38") (name "Net-(J1-Pad3)") (class "Default")
      (node (ref "J1") (pin "3") (pinfunction "3_3") (pintype "passive"))
      (node (ref "R2") (pin "1") (pinfunction "1_1") (pintype "passive"))
    )
    (net (code "39") (name "Net-(J2-Pad2)") (class "Default")
      (node (ref "J2") (pin "2") (pinfunction "2_2") (pintype "passive"))
      (node (ref "R3") (pin "1") (pinfunction "1_1") (pintype "passive"))
    )
    (net (code "40") (name "Net-(J2-Pad3)") (class "Default")
      (node (ref "J2") (pin "3") (pinfunction "3_3") (pintype "passive"))
      (node (ref "R4") (pin "1") (pinfunction "1_1") (pintype "passive"))
    )
    (net (code "41") (name "Net-(LED1-DO)") (class "Default")
      (node (ref "LED1") (pin "2-DOUT") (pinfunction "DO_2-DOUT") (pintype "output"))
      (node (ref "LED2") (pin "4-DIN") (pinfunction "DI_4-DIN") (pintype "input"))
    )
    (net (code "42") (name "Net-(LED1-VDD)") (class "Default")
      (node (ref "C1") (pin "1") (pinfunction "1_1") (pintype "passive"))
      (node (ref "D21") (pin "C") (pinfunction "C_C") (pintype "passive"))
      (node (ref "LED1") (pin "1-VDD") (pinfunction "VDD_1-VDD") (pintype "power_in"))
    )
    (net (code "43") (name "Net-(LED2-DO)") (class "Default")
      (node (ref "LED2") (pin "2-DOUT") (pinfunction "DO_2-DOUT") (pintype "output"))
      (node (ref "LED3") (pin "4-DIN") (pinfunction "DI_4-DIN") (pintype "input"))
    )
    (net (code "44") (name "Net-(LED3-DO)") (class "Default")
      (node (ref "LED3") (pin "2-DOUT") (pinfunction "DO_2-DOUT") (pintype "output"))
      (node (ref "LED4") (pin "4-DIN") (pinfunction "DI_4-DIN") (pintype "input"))
    )
    (net (code "45") (name "Net-(LED4-DO)") (class "Default")
      (node (ref "LED4") (pin "2-DOUT") (pinfunction "DO_2-DOUT") (pintype "output"))
      (node (ref "LED5") (pin "4-DIN") (pinfunction "DI_4-DIN") (pintype "input"))
    )
    (net (code "46") (name "Net-(LED5-DO)") (class "Default")
      (node (ref "LED5") (pin "2-DOUT") (pinfunction "DO_2-DOUT") (pintype "output"))
      (node (ref "LED6") (pin "4-DIN") (pinfunction "DI_4-DIN") (pintype "input"))
    )
    (net (code "47") (name "Net-(LED6-DO)") (class "Default")
      (node (ref "LED6") (pin "2-DOUT") (pinfunction "DO_2-DOUT") (pintype "output"))
      (node (ref "LED7") (pin "4-DIN") (pinfunction "DI_4-DIN") (pintype "input"))
    )
    (net (code "48") (name "Net-(LED7-DO)") (class "Default")
      (node (ref "LED7") (pin "2-DOUT") (pinfunction "DO_2-DOUT") (pintype "output"))
      (node (ref "LED8") (pin "4-DIN") (pinfunction "DI_4-DIN") (pintype "input"))
    )
    (net (code "49") (name "Net-(LED8-DO)") (class "Default")
      (node (ref "LED8") (pin "2-DOUT") (pinfunction "DO_2-DOUT") (pintype "output"))
      (node (ref "LED9") (pin "4-DIN") (pinfunction "DI_4-DIN") (pintype "input"))
    )
    (net (code "50") (name "Net-(LED10-DI)") (class "Default")
      (node (ref "LED10") (pin "4-DIN") (pinfunction "DI_4-DIN") (pintype "input"))
      (node (ref "LED9") (pin "2-DOUT") (pinfunction "DO_2-DOUT") (pintype "output"))
    )
    (net (code "51") (name "Net-(LED10-DO)") (class "Default")
      (node (ref "LED10") (pin "2-DOUT") (pinfunction "DO_2-DOUT") (pintype "output"))
      (node (ref "LED11") (pin "4-DIN") (pinfunction "DI_4-DIN") (pintype "input"))
    )
    (net (code "52") (name "Net-(LED11-DO)") (class "Default")
      (node (ref "LED11") (pin "2-DOUT") (pinfunction "DO_2-DOUT") (pintype "output"))
      (node (ref "LED12") (pin "4-DIN") (pinfunction "DI_4-DIN") (pintype "input"))
    )
    (net (code "53") (name "Net-(LED12-DO)") (class "Default")
      (node (ref "LED12") (pin "2-DOUT") (pinfunction "DO_2-DOUT") (pintype "output"))
      (node (ref "LED13") (pin "4-DIN") (pinfunction "DI_4-DIN") (pintype "input"))
    )
    (net (code "54") (name "Net-(LED13-DO)") (class "Default")
      (node (ref "LED13") (pin "2-DOUT") (pinfunction "DO_2-DOUT") (pintype "output"))
      (node (ref "LED14") (pin "4-DIN") (pinfunction "DI_4-DIN") (pintype "input"))
    )
    (net (code "55") (name "Net-(LED14-DO)") (class "Default")
      (node (ref "LED14") (pin "2-DOUT") (pinfunction "DO_2-DOUT") (pintype "output"))
      (node (ref "LED15") (pin "4-DIN") (pinfunction "DI_4-DIN") (pintype "input"))
    )
    (net (code "56") (name "Net-(LED15-DO)") (class "Default")
      (node (ref "LED15") (pin "2-DOUT") (pinfunction "DO_2-DOUT") (pintype "output"))
      (node (ref "LED16") (pin "4-DIN") (pinfunction "DI_4-DIN") (pintype "input"))
    )
    (net (code "57") (name "Net-(LED16-DO)") (class "Default")
      (node (ref "LED16") (pin "2-DOUT") (pinfunction "DO_2-DOUT") (pintype "output"))
      (node (ref "LED17") (pin "4-DIN") (pinfunction "DI_4-DIN") (pintype "input"))
    )
    (net (code "58") (name "Net-(LED17-DO)") (class "Default")
      (node (ref "LED17") (pin "2-DOUT") (pinfunction "DO_2-DOUT") (pintype "output"))
      (node (ref "LED18") (pin "4-DIN") (pinfunction "DI_4-DIN") (pintype "input"))
    )
    (net (code "59") (name "Net-(LED18-DO)") (class "Default")
      (node (ref "LED18") (pin "2-DOUT") (pinfunction "DO_2-DOUT") (pintype "output"))
      (node (ref "LED19") (pin "4-DIN") (pinfunction "DI_4-DIN") (pintype "input"))
    )
    (net (code "60") (name "Net-(LED19-DO)") (class "Default")
      (node (ref "LED19") (pin "2-DOUT") (pinfunction "DO_2-DOUT") (pintype "output"))
      (node (ref "LED20") (pin "4-DIN") (pinfunction "DI_4-DIN") (pintype "input"))
    )
    (net (code "61") (name "Net-(U1-TXO)") (class "Default")
      (node (ref "R1") (pin "2") (pinfunction "2_2") (pintype "passive"))
      (node (ref "U1") (pin "1") (pinfunction "TXO_1") (pintype "bidirectional"))
    )
    (net (code "62") (name "unconnected-(LED20-DO-Pad2-DOUT)") (class "Default")
      (node (ref "LED20") (pin "2-DOUT") (pinfunction "DO_2-DOUT") (pintype "output"))
    )
    (net (code "63") (name "unconnected-(U1-13(SCK)-Pad16)") (class "Default")
      (node (ref "U1") (pin "16") (pinfunction "13(SCK)_16") (pintype "bidirectional"))
    )
    (net (code "64") (name "unconnected-(U1-A0-Pad17)") (class "Default")
      (node (ref "U1") (pin "17") (pinfunction "A0_17") (pintype "bidirectional"))
    )
    (net (code "65") (name "unconnected-(U1-A1-Pad18)") (class "Default")
      (node (ref "U1") (pin "18") (pinfunction "A1_18") (pintype "bidirectional"))
    )
    (net (code "66") (name "unconnected-(U1-A2-Pad19)") (class "Default")
      (node (ref "U1") (pin "19") (pinfunction "A2_19") (pintype "bidirectional"))
    )
    (net (code "67") (name "unconnected-(U1-A3-Pad20)") (class "Default")
      (node (ref "U1") (pin "20") (pinfunction "A3_20") (pintype "bidirectional"))
    )
    (net (code "68") (name "unconnected-(U1-RESET-Pad22)") (class "Default")
      (node (ref "U1") (pin "22") (pinfunction "RESET_22") (pintype "bidirectional"))
    )
    (net (code "69") (name "unconnected-(U1-RXI-Pad2)") (class "Default")
      (node (ref "U1") (pin "2") (pinfunction "RXI_2") (pintype "bidirectional"))
    )
  )
)
